# Mach3led.net
KiCad netlist of a schematic drawn in Altium Designer
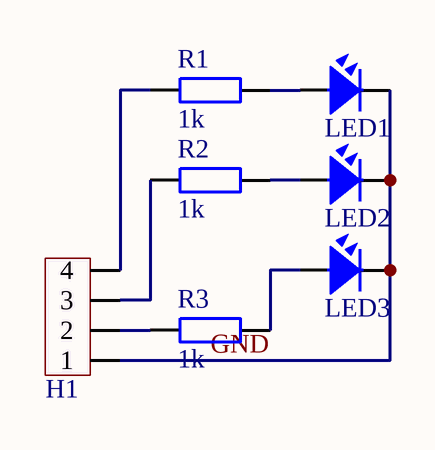
[diagram p0: Mach3led.SchDoc]

(export (version "E")
  (design (tool "Eeschema 10.0.6"))
  (components
    (comp (ref "H1")
      (value "Header4")
      (footprint "Header4")
      (description "Header IDC, 4 x 1 Pin Vertical 2.54mm Pitch (Non-Boxed, Male)")
      (libsource (lib "LIBRARY") (part "Header4"))
    )
    (comp (ref "LED1")
      (value "LED")
      (footprint "LED-3")
      (description "LED Single colour Green and Red")
      (libsource (lib "syhaunguyen") (part "LED"))
    )
    (comp (ref "LED2")
      (value "LED")
      (footprint "LED-3")
      (description "LED Single colour Green and Red")
      (libsource (lib "syhaunguyen") (part "LED"))
    )
    (comp (ref "LED3")
      (value "LED")
      (footprint "LED-3")
      (description "LED Single colour Green and Red")
      (libsource (lib "syhaunguyen") (part "LED"))
    )
    (comp (ref "R1")
      (value "1k")
      (footprint "R1/4W")
      (description "Resistor 1/4W")
      (libsource (lib "syhaunguyen") (part "R1/4W"))
    )
    (comp (ref "R2")
      (value "1k")
      (footprint "R1/4W")
      (description "Resistor 1/4W")
      (libsource (lib "syhaunguyen") (part "R1/4W"))
    )
    (comp (ref "R3")
      (value "1k")
      (footprint "R1/4W")
      (description "Resistor 1/4W")
      (libsource (lib "syhaunguyen") (part "R1/4W"))
    )
  )
  (nets
    (net (code "1") (name "/GND") (class "Default")
      (node (ref "H1") (pin "1") (pinfunction "1_1") (pintype "passive"))
      (node (ref "LED1") (pin "2") (pinfunction "2_2") (pintype "passive"))
      (node (ref "LED2") (pin "2") (pinfunction "2_2") (pintype "passive"))
      (node (ref "LED3") (pin "2") (pinfunction "2_2") (pintype "passive"))
    )
    (net (code "2") (name "Net-(H1-Pad2)") (class "Default")
      (node (ref "H1") (pin "2") (pinfunction "2_2") (pintype "passive"))
      (node (ref "R3") (pin "1") (pinfunction "1_1") (pintype "passive"))
    )
    (net (code "3") (name "Net-(H1-Pad3)") (class "Default")
      (node (ref "H1") (pin "3") (pinfunction "3_3") (pintype "passive"))
      (node (ref "R2") (pin "1") (pinfunction "1_1") (pintype "passive"))
    )
    (net (code "4") (name "Net-(H1-Pad4)") (class "Default")
      (node (ref "H1") (pin "4") (pinfunction "4_4") (pintype "passive"))
      (node (ref "R1") (pin "1") (pinfunction "1_1") (pintype "passive"))
    )
    (net (code "5") (name "Net-(LED1-Pad1)") (class "Default")
      (node (ref "LED1") (pin "1") (pinfunction "1_1") (pintype "passive"))
      (node (ref "R1") (pin "2") (pinfunction "2_2") (pintype "passive"))
    )
    (net (code "6") (name "Net-(LED2-Pad1)") (class "Default")
      (node (ref "LED2") (pin "1") (pinfunction "1_1") (pintype "passive"))
      (node (ref "R2") (pin "2") (pinfunction "2_2") (pintype "passive"))
    )
    (net (code "7") (name "Net-(LED3-Pad1)") (class "Default")
      (node (ref "LED3") (pin "1") (pinfunction "1_1") (pintype "passive"))
      (node (ref "R3") (pin "2") (pinfunction "2_2") (pintype "passive"))
    )
  )
)
